# Expansion.net
KiCad netlist of a schematic drawn in Altium Designer
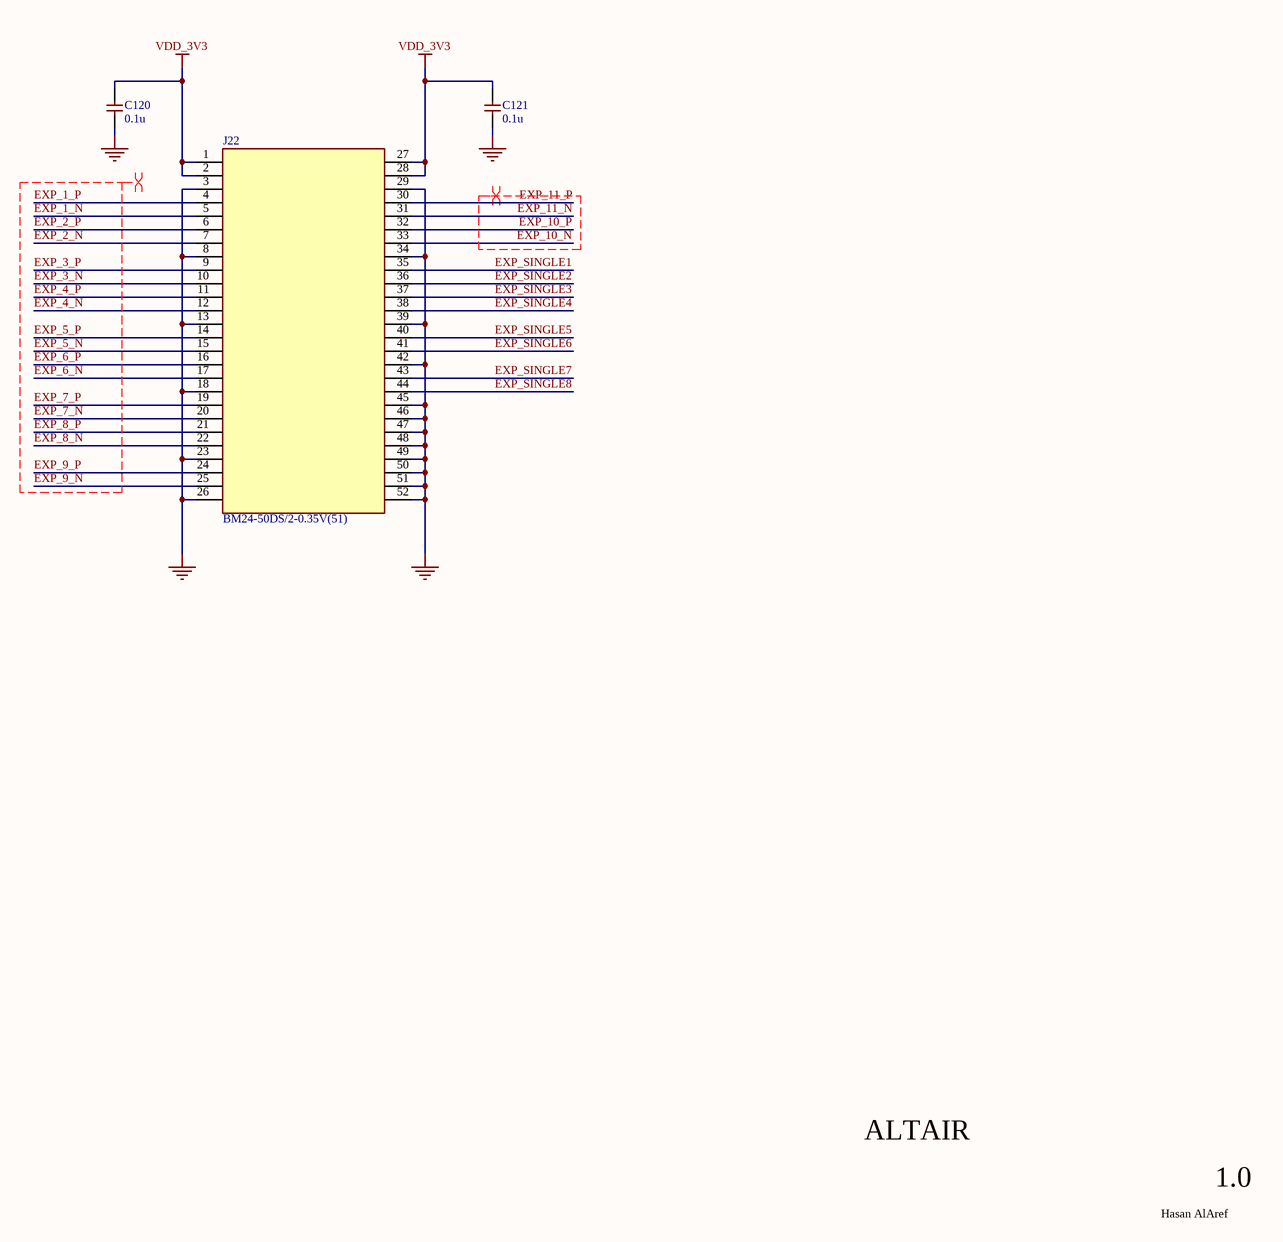
[diagram p0: Expansion.SchDoc]

(export (version "E")
  (design (tool "Eeschema 10.0.6"))
  (components
    (comp (ref "C120")
      (value "0.1u")
      (footprint "CAP_0402")
      (description "Capacitor SMD 0402")
      (fields (field (name "PART NO") "CL05B104KO5NNNC") (field (name "JLCPCB PART #") "C338112"))
      (libsource (lib "personalGenericLib") (part "CAP_0402"))
    )
    (comp (ref "C121")
      (value "0.1u")
      (footprint "CAP_0402")
      (description "Capacitor SMD 0402")
      (fields (field (name "PART NO") "CL05B104KO5NNNC") (field (name "JLCPCB PART #") "C338112"))
      (libsource (lib "personalGenericLib") (part "CAP_0402"))
    )
    (comp (ref "J22")
      (value "BM24-50DS/2-0.35V(51)")
      (footprint "BM24-50DS/2-0.35V(51)")
      (description "BTB Connector")
      (fields (field (name "JLCPCB PART #") "C424561"))
      (libsource (lib "personalGenericLib") (part "BM24-50DS/2-0.35V(51)"))
    )
  )
  (nets
    (net (code "1") (name "/EXP_1_N") (class "Default")
      (node (ref "J22") (pin "5") (pinfunction "5_5") (pintype "passive"))
    )
    (net (code "2") (name "/EXP_1_P") (class "Default")
      (node (ref "J22") (pin "4") (pinfunction "4_4") (pintype "passive"))
    )
    (net (code "3") (name "/EXP_2_N") (class "Default")
      (node (ref "J22") (pin "7") (pinfunction "7_7") (pintype "passive"))
    )
    (net (code "4") (name "/EXP_2_P") (class "Default")
      (node (ref "J22") (pin "6") (pinfunction "6_6") (pintype "passive"))
    )
    (net (code "5") (name "/EXP_3_N") (class "Default")
      (node (ref "J22") (pin "10") (pinfunction "10_10") (pintype "passive"))
    )
    (net (code "6") (name "/EXP_3_P") (class "Default")
      (node (ref "J22") (pin "9") (pinfunction "9_9") (pintype "passive"))
    )
    (net (code "7") (name "/EXP_4_N") (class "Default")
      (node (ref "J22") (pin "12") (pinfunction "12_12") (pintype "passive"))
    )
    (net (code "8") (name "/EXP_4_P") (class "Default")
      (node (ref "J22") (pin "11") (pinfunction "11_11") (pintype "passive"))
    )
    (net (code "9") (name "/EXP_5_N") (class "Default")
      (node (ref "J22") (pin "15") (pinfunction "15_15") (pintype "passive"))
    )
    (net (code "10") (name "/EXP_5_P") (class "Default")
      (node (ref "J22") (pin "14") (pinfunction "14_14") (pintype "passive"))
    )
    (net (code "11") (name "/EXP_6_N") (class "Default")
      (node (ref "J22") (pin "17") (pinfunction "0_17") (pintype "passive"))
    )
    (net (code "12") (name "/EXP_6_P") (class "Default")
      (node (ref "J22") (pin "16") (pinfunction "0_16") (pintype "passive"))
    )
    (net (code "13") (name "/EXP_7_N") (class "Default")
      (node (ref "J22") (pin "20") (pinfunction "0_20") (pintype "passive"))
    )
    (net (code "14") (name "/EXP_7_P") (class "Default")
      (node (ref "J22") (pin "19") (pinfunction "0_19") (pintype "passive"))
    )
    (net (code "15") (name "/EXP_8_N") (class "Default")
      (node (ref "J22") (pin "22") (pinfunction "0_22") (pintype "passive"))
    )
    (net (code "16") (name "/EXP_8_P") (class "Default")
      (node (ref "J22") (pin "21") (pinfunction "0_21") (pintype "passive"))
    )
    (net (code "17") (name "/EXP_9_N") (class "Default")
      (node (ref "J22") (pin "25") (pinfunction "0_25") (pintype "passive"))
    )
    (net (code "18") (name "/EXP_9_P") (class "Default")
      (node (ref "J22") (pin "24") (pinfunction "0_24") (pintype "passive"))
    )
    (net (code "19") (name "/EXP_10_N") (class "Default")
      (node (ref "J22") (pin "33") (pinfunction "0_33") (pintype "passive"))
    )
    (net (code "20") (name "/EXP_10_P") (class "Default")
      (node (ref "J22") (pin "32") (pinfunction "0_32") (pintype "passive"))
    )
    (net (code "21") (name "/EXP_11_N") (class "Default")
      (node (ref "J22") (pin "31") (pinfunction "0_31") (pintype "passive"))
    )
    (net (code "22") (name "/EXP_11_P") (class "Default")
      (node (ref "J22") (pin "30") (pinfunction "0_30") (pintype "passive"))
    )
    (net (code "23") (name "/EXP_SINGLE1") (class "Default")
      (node (ref "J22") (pin "35") (pinfunction "0_35") (pintype "passive"))
    )
    (net (code "24") (name "/EXP_SINGLE2") (class "Default")
      (node (ref "J22") (pin "36") (pinfunction "0_36") (pintype "passive"))
    )
    (net (code "25") (name "/EXP_SINGLE3") (class "Default")
      (node (ref "J22") (pin "37") (pinfunction "0_37") (pintype "passive"))
    )
    (net (code "26") (name "/EXP_SINGLE4") (class "Default")
      (node (ref "J22") (pin "38") (pinfunction "0_38") (pintype "passive"))
    )
    (net (code "27") (name "/EXP_SINGLE5") (class "Default")
      (node (ref "J22") (pin "40") (pinfunction "0_40") (pintype "passive"))
    )
    (net (code "28") (name "/EXP_SINGLE6") (class "Default")
      (node (ref "J22") (pin "41") (pinfunction "0_41") (pintype "passive"))
    )
    (net (code "29") (name "/EXP_SINGLE7") (class "Default")
      (node (ref "J22") (pin "43") (pinfunction "0_43") (pintype "passive"))
    )
    (net (code "30") (name "/EXP_SINGLE8") (class "Default")
      (node (ref "J22") (pin "44") (pinfunction "0_44") (pintype "passive"))
    )
    (net (code "31") (name "GND") (class "Default")
      (node (ref "C120") (pin "1") (pinfunction "1_1") (pintype "passive"))
      (node (ref "C121") (pin "1") (pinfunction "1_1") (pintype "passive"))
      (node (ref "J22") (pin "13") (pinfunction "13_13") (pintype "passive"))
      (node (ref "J22") (pin "18") (pinfunction "0_18") (pintype "passive"))
      (node (ref "J22") (pin "23") (pinfunction "0_23") (pintype "passive"))
      (node (ref "J22") (pin "26") (pinfunction "0_26") (pintype "passive"))
      (node (ref "J22") (pin "29") (pinfunction "0_29") (pintype "passive"))
      (node (ref "J22") (pin "3") (pinfunction "3_3") (pintype "passive"))
      (node (ref "J22") (pin "34") (pinfunction "0_34") (pintype "passive"))
      (node (ref "J22") (pin "39") (pinfunction "0_39") (pintype "passive"))
      (node (ref "J22") (pin "42") (pinfunction "0_42") (pintype "passive"))
      (node (ref "J22") (pin "45") (pinfunction "0_45") (pintype "passive"))
      (node (ref "J22") (pin "46") (pinfunction "0_46") (pintype "passive"))
      (node (ref "J22") (pin "47") (pinfunction "0_47") (pintype "passive"))
      (node (ref "J22") (pin "48") (pinfunction "0_48") (pintype "passive"))
      (node (ref "J22") (pin "49") (pinfunction "0_49") (pintype "passive"))
      (node (ref "J22") (pin "50") (pinfunction "0_50") (pintype "passive"))
      (node (ref "J22") (pin "51") (pinfunction "0_51") (pintype "passive"))
      (node (ref "J22") (pin "52") (pinfunction "0_52") (pintype "passive"))
      (node (ref "J22") (pin "8") (pinfunction "8_8") (pintype "passive"))
    )
    (net (code "32") (name "VDD_3V3") (class "Default")
      (node (ref "C120") (pin "2") (pinfunction "2_2") (pintype "passive"))
      (node (ref "C121") (pin "2") (pinfunction "2_2") (pintype "passive"))
      (node (ref "J22") (pin "1") (pinfunction "1_1") (pintype "passive"))
      (node (ref "J22") (pin "2") (pinfunction "2_2") (pintype "passive"))
      (node (ref "J22") (pin "27") (pinfunction "0_27") (pintype "passive"))
      (node (ref "J22") (pin "28") (pinfunction "0_28") (pintype "passive"))
    )
  )
)
